# Relay.net
KiCad netlist of a schematic drawn in EAGLE
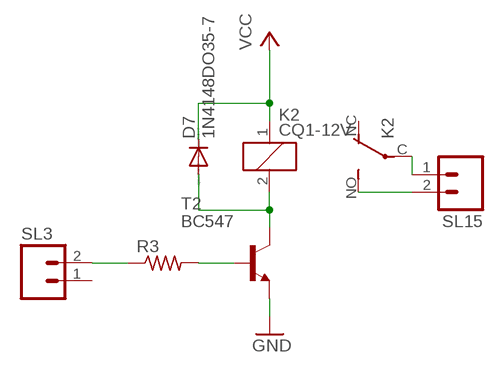
[diagram p0: schematic, sheet 1]

(export (version "E")
  (design (tool "Eeschema 10.0.6"))
  (components
    (comp (ref "D7")
      (value "1N4148DO35-7")
      (footprint "eagle-import:DO35-7")
      (libsource (lib "eagle-import") (part "1N4148DO35-7"))
    )
    (comp (ref "K2")
      (value "CQ1-12V")
      (footprint "eagle-import:CQ1")
      (libsource (lib "eagle-import") (part "CQ1-12V"))
    )
    (comp (ref "R3")
      (value "R-US_0204/7")
      (footprint "eagle-import:0204_7")
      (libsource (lib "eagle-import") (part "R-US_0204/7"))
    )
    (comp (ref "SL3")
      (value "M02")
      (footprint "eagle-import:02P")
      (libsource (lib "eagle-import") (part "M02"))
    )
    (comp (ref "SL15")
      (value "M02")
      (footprint "eagle-import:02P")
      (libsource (lib "eagle-import") (part "M02"))
    )
    (comp (ref "T2")
      (value "BC547")
      (footprint "eagle-import:TO92")
      (libsource (lib "eagle-import") (part "BC547"))
    )
  )
  (nets
    (net (code "1") (name "GND") (class "Default")
      (node (ref "T2") (pin "1") (pinfunction "E_1") (pintype "passive"))
    )
    (net (code "2") (name "Net-(K2B-P)") (class "Default")
      (node (ref "K2") (pin "C") (pinfunction "P_C") (pintype "passive"))
      (node (ref "SL15") (pin "1") (pinfunction "1_1") (pintype "passive"))
    )
    (net (code "3") (name "Net-(K2B-S)") (class "Default")
      (node (ref "K2") (pin "NO") (pinfunction "S_NO") (pintype "passive"))
      (node (ref "SL15") (pin "2") (pinfunction "2_2") (pintype "passive"))
    )
    (net (code "4") (name "Net-(R3-Pad1)") (class "Default")
      (node (ref "R3") (pin "1") (pinfunction "1_1") (pintype "passive"))
      (node (ref "SL3") (pin "2") (pinfunction "2_2") (pintype "passive"))
    )
    (net (code "5") (name "Net-(T2-B)") (class "Default")
      (node (ref "R3") (pin "2") (pinfunction "2_2") (pintype "passive"))
      (node (ref "T2") (pin "2") (pinfunction "B_2") (pintype "passive"))
    )
    (net (code "6") (name "Net-(T2-C)") (class "Default")
      (node (ref "D7") (pin "A") (pinfunction "A_A") (pintype "passive"))
      (node (ref "K2") (pin "2") (pinfunction "2_2") (pintype "passive"))
      (node (ref "T2") (pin "3") (pinfunction "C_3") (pintype "passive"))
    )
    (net (code "7") (name "VCC") (class "Default")
      (node (ref "D7") (pin "C") (pinfunction "C_C") (pintype "passive"))
      (node (ref "K2") (pin "1") (pinfunction "1_1") (pintype "passive"))
    )
    (net (code "8") (name "unconnected-(K2B-O-PadNC)") (class "Default")
      (node (ref "K2") (pin "NC") (pinfunction "O_NC") (pintype "passive"))
    )
    (net (code "9") (name "unconnected-(SL3-Pad1)") (class "Default")
      (node (ref "SL3") (pin "1") (pinfunction "1_1") (pintype "passive"))
    )
  )
)
